# LDO3v3.net
KiCad netlist of a schematic drawn in Altium Designer
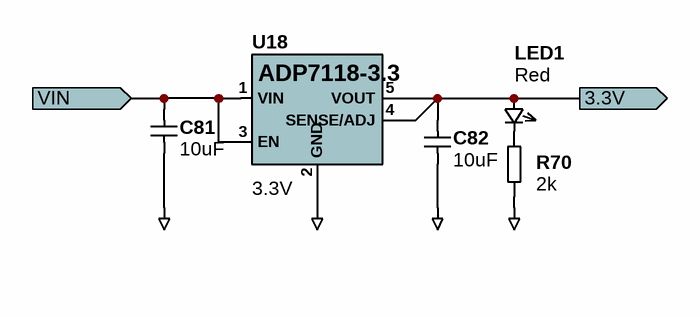
[diagram p0: LDO3v3.SchDoc]

(export (version "E")
  (design (tool "Eeschema 10.0.6"))
  (components
    (comp (ref "C81")
      (value "10uF")
      (footprint "1206-capacitor")
      (description "Capacitor 1206")
      (fields (field (name "TOLERANCE") "±20%"))
      (libsource (lib "PRL_PDC") (part "C_1206"))
    )
    (comp (ref "C82")
      (value "10uF")
      (footprint "1206-capacitor")
      (description "Capacitor 1206")
      (fields (field (name "TOLERANCE") "±20%"))
      (libsource (lib "PRL_PDC") (part "C_1206"))
    )
    (comp (ref "LED1") (value "Red") (footprint "LED0603") (libsource (lib "PRL_PDC") (part "LED0603")))
    (comp (ref "R70")
      (value "2k")
      (footprint "0402-RESISTOR")
      (description "Resistor 0402")
      (fields (field (name "TOLERANCE") "±1%"))
      (libsource (lib "PRL_PDC") (part "R_0402"))
    )
    (comp (ref "U18")
      (value "3.3V")
      (footprint "SOT-23-5")
      (description "20 V, 200 mA, Low Noise,\r\nCMOS LDO Linear Regulator")
      (libsource (lib "PRL_PDC") (part "ADP7118-3.3"))
    )
  )
  (nets
    (net (code "1") (name "/3.3V") (class "Default")
      (node (ref "C82") (pin "1") (pinfunction "1_1") (pintype "passive"))
      (node (ref "LED1") (pin "A") (pinfunction "A_A") (pintype "passive"))
      (node (ref "U18") (pin "4") (pinfunction "SENSE/ADJ_4") (pintype "passive"))
      (node (ref "U18") (pin "5") (pinfunction "VOUT_5") (pintype "passive"))
    )
    (net (code "2") (name "/VIN") (class "Default")
      (node (ref "C81") (pin "1") (pinfunction "1_1") (pintype "passive"))
      (node (ref "U18") (pin "1") (pinfunction "VIN_1") (pintype "passive"))
      (node (ref "U18") (pin "3") (pinfunction "EN_3") (pintype "passive"))
    )
    (net (code "3") (name "GND") (class "Default")
      (node (ref "C81") (pin "2") (pinfunction "2_2") (pintype "passive"))
      (node (ref "C82") (pin "2") (pinfunction "2_2") (pintype "passive"))
      (node (ref "R70") (pin "1") (pinfunction "1_1") (pintype "passive"))
      (node (ref "U18") (pin "2") (pinfunction "GND_2") (pintype "passive"))
    )
    (net (code "4") (name "Net-(LED1-PadK)") (class "Default")
      (node (ref "LED1") (pin "K") (pinfunction "K_K") (pintype "passive"))
      (node (ref "R70") (pin "2") (pinfunction "2_2") (pintype "passive"))
    )
  )
)
